# 4_cyber60-2_power.net
KiCad netlist of a schematic drawn in Altium Designer
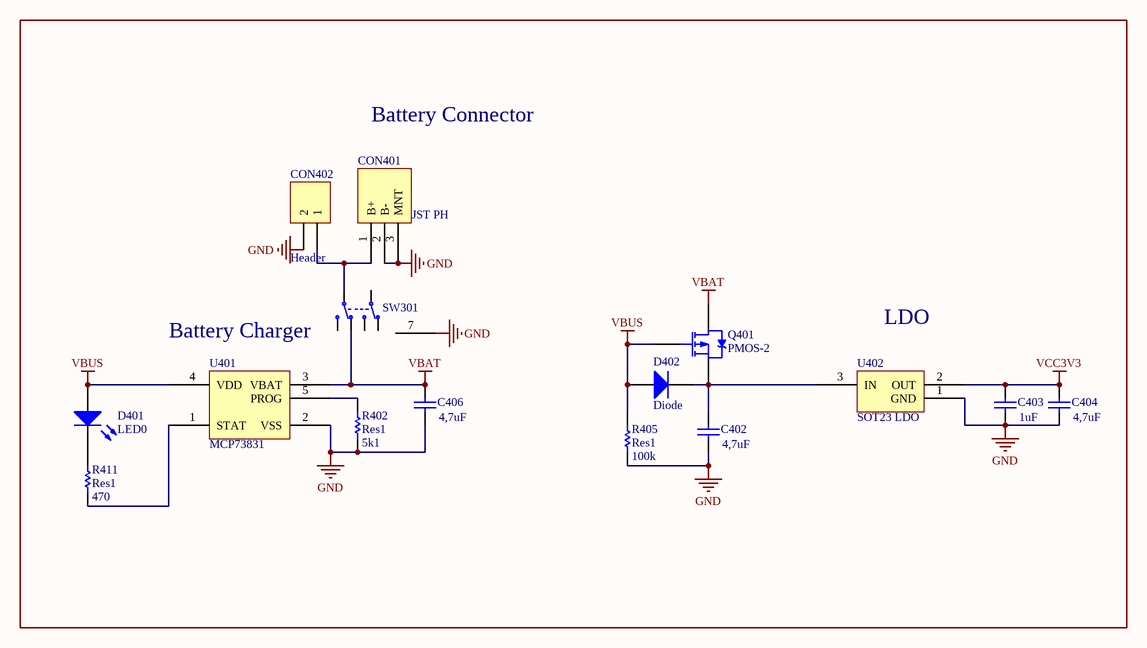
[diagram p0: 4_cyber60-2_power.SchDoc]

(export (version "E")
  (design (tool "Eeschema 10.0.6"))
  (components
    (comp (ref "C402")
      (value "4,7uF")
      (footprint "C0603[1608]")
      (description "Capacitor")
      (fields (field (name "LCSC PART #") "C19666") (field (name "MRF.PART") "CL10A475KO8NNNC"))
      (libsource (lib "Miscellaneous Devices") (part "Cap"))
    )
    (comp (ref "C403")
      (value "1uF")
      (footprint "C0603[1608]")
      (description "Capacitor")
      (fields (field (name "MFG") "KEMET") (field (name "LCSC PART #") "C15849"))
      (libsource (lib "Miscellaneous Devices") (part "Cap"))
    )
    (comp (ref "C404")
      (value "4,7uF")
      (footprint "C0603[1608]")
      (description "Capacitor")
      (fields (field (name "LCSC PART #") "C19666") (field (name "MRF.PART") "CL10A475KO8NNNC"))
      (libsource (lib "Miscellaneous Devices") (part "Cap"))
    )
    (comp (ref "C406")
      (value "4,7uF")
      (footprint "C0603[1608]")
      (description "Capacitor")
      (fields (field (name "LCSC PART #") "C19666") (field (name "MRF.PART") "CL10A475KO8NNNC"))
      (libsource (lib "Miscellaneous Devices") (part "Cap"))
    )
    (comp (ref "CON401")
      (value "JST PH")
      (footprint "JST SM02B-SRSS-TB")
      (fields (field (name "LCSC PART #") "C160402") (field (name "MRF.PART") "SM02B-SRSS-TB(LF)(SN)"))
      (libsource (lib "Keebs") (part "JST S2B-PH-SM4-TB"))
    )
    (comp (ref "CON402")
      (value "Header")
      (footprint "Keebs:JST S2B-PH-K(LF)(SN)")
      (description "Header, 2-Pin")
      (fields (field (name "LCSC PART #") "C265016") (field (name "MRF.PART") "S2B-PH-K(LF)(SN)"))
      (libsource (lib "Miscellaneous Connectors") (part "Header 2"))
    )
    (comp (ref "D401")
      (value "LED0")
      (footprint "LED0603[1608]")
      (description "Typical INFRARED GaAs LED")
      (fields (field (name "LCSC PART #") "C72038") (field (name "MRF.PART") "19-213/Y2C-CQ2R2L/3T(CY)"))
      (libsource (lib "Miscellaneous Devices") (part "LED0"))
    )
    (comp (ref "D402")
      (value "Diode")
      (footprint "SOD-123")
      (description "Default Diode")
      (fields (field (name "LCSC PART #") "C8598") (field (name "MRF.PART") "B5819W"))
      (libsource (lib "Miscellaneous Devices") (part "Diode"))
    )
    (comp (ref "Q401")
      (value "PMOS-2")
      (footprint "SOT-23-3")
      (description "P-Channel Power MOSFET")
      (fields (field (name "MRF.PART") "SI2301CDS-T1-GE3") (field (name "LCSC PART #") "C10487"))
      (libsource (lib "Miscellaneous Devices") (part "PMOS-2"))
    )
    (comp (ref "R402")
      (value "Res1")
      (footprint "R0603[1608]")
      (description "Resistor")
      (fields
        (field (name "ALTIUM_VALUE") "5k1")
        (field (name "MFG") "Panasonic Electronic Components")
        (field (name "LCSC PART #") "C23186")
      )
      (libsource (lib "Miscellaneous Devices") (part "Res1"))
    )
    (comp (ref "R405")
      (value "Res1")
      (footprint "R0603[1608]")
      (description "Resistor")
      (fields
        (field (name "ALTIUM_VALUE") "100k")
        (field (name "MRF.PART") "0603WAF1003T5E")
        (field (name "LCSC PART #") "C25803")
      )
      (libsource (lib "Miscellaneous Devices") (part "Res1"))
    )
    (comp (ref "R411")
      (value "Res1")
      (footprint "R0603[1608]")
      (description "Resistor")
      (fields
        (field (name "ALTIUM_VALUE") "470")
        (field (name "MFG") "Panasonic Electronic Components")
        (field (name "LCSC PART #") "C23179")
      )
      (libsource (lib "Miscellaneous Devices") (part "Res1"))
    )
    (comp (ref "SW301")
      (value "~")
      (footprint "AlpsAlpine SSSS820201")
      (description "Slide Switch DPDT")
      (fields (field (name "MRF.PART") "SSSS820201") (field (name "LCSC PART #") "C160879"))
      (libsource (lib "Keebs") (part "MKH-22D14-G2-B"))
    )
    (comp (ref "U401")
      (value "MCP73831")
      (footprint "SOT-23-5")
      (fields (field (name "LCSC PART #") "C32574") (field (name "MRF.PART") "TP4054"))
      (libsource (lib "Keebs") (part "MCP73831"))
    )
    (comp (ref "U402")
      (value "SOT23 LDO")
      (footprint "SOT-23-3")
      (fields
        (field (name "LCSC PART #") "C5446")
        (field (name "MRF.PART") "XC6206P332MR")
        (field (name "MFG") "Texas Instruments")
      )
      (libsource (lib "Keebs") (part "SOT23 LDO"))
    )
  )
  (nets
    (net (code "1") (name "GND") (class "Default")
      (node (ref "C402") (pin "1") (pinfunction "1_1") (pintype "passive"))
      (node (ref "C403") (pin "1") (pinfunction "1_1") (pintype "passive"))
      (node (ref "C404") (pin "1") (pinfunction "1_1") (pintype "passive"))
      (node (ref "C406") (pin "1") (pinfunction "1_1") (pintype "passive"))
      (node (ref "CON401") (pin "2") (pinfunction "B-_2") (pintype "passive"))
      (node (ref "CON401") (pin "3") (pinfunction "MNT_3") (pintype "passive"))
      (node (ref "CON402") (pin "2") (pinfunction "2_2") (pintype "passive"))
      (node (ref "R402") (pin "2") (pinfunction "2_2") (pintype "passive"))
      (node (ref "R405") (pin "2") (pinfunction "2_2") (pintype "passive"))
      (node (ref "SW301") (pin "7") (pinfunction "MNT_7") (pintype "passive"))
      (node (ref "U401") (pin "2") (pinfunction "VSS_2") (pintype "passive"))
      (node (ref "U402") (pin "1") (pinfunction "GND_1") (pintype "passive"))
    )
    (net (code "2") (name "Net-(CON401-B+)") (class "Default")
      (node (ref "CON401") (pin "1") (pinfunction "B+_1") (pintype "passive"))
      (node (ref "CON402") (pin "1") (pinfunction "1_1") (pintype "passive"))
      (node (ref "SW301") (pin "5") (pinfunction "COM-2_5") (pintype "passive"))
    )
    (net (code "3") (name "Net-(D401-K)") (class "Default")
      (node (ref "D401") (pin "2") (pinfunction "K_2") (pintype "passive"))
      (node (ref "R411") (pin "2") (pinfunction "2_2") (pintype "passive"))
    )
    (net (code "4") (name "Net-(D402-K)") (class "Default")
      (node (ref "C402") (pin "2") (pinfunction "2_2") (pintype "passive"))
      (node (ref "D402") (pin "2") (pinfunction "K_2") (pintype "passive"))
      (node (ref "Q401") (pin "2") (pinfunction "S_2") (pintype "passive"))
      (node (ref "U402") (pin "3") (pinfunction "IN_3") (pintype "passive"))
    )
    (net (code "5") (name "Net-(U401-PROG)") (class "Default")
      (node (ref "R402") (pin "1") (pinfunction "1_1") (pintype "passive"))
      (node (ref "U401") (pin "5") (pinfunction "PROG_5") (pintype "passive"))
    )
    (net (code "6") (name "Net-(U401-STAT)") (class "Default")
      (node (ref "R411") (pin "1") (pinfunction "1_1") (pintype "passive"))
      (node (ref "U401") (pin "1") (pinfunction "STAT_1") (pintype "passive"))
    )
    (net (code "7") (name "VBAT") (class "Default")
      (node (ref "C406") (pin "2") (pinfunction "2_2") (pintype "passive"))
      (node (ref "Q401") (pin "3") (pinfunction "D_3") (pintype "passive"))
      (node (ref "SW301") (pin "6") (pinfunction "N.C-2_6") (pintype "passive"))
      (node (ref "U401") (pin "3") (pinfunction "VBAT_3") (pintype "passive"))
    )
    (net (code "8") (name "VBUS") (class "Default")
      (node (ref "D401") (pin "1") (pinfunction "A_1") (pintype "passive"))
      (node (ref "D402") (pin "1") (pinfunction "A_1") (pintype "passive"))
      (node (ref "Q401") (pin "1") (pinfunction "G_1") (pintype "passive"))
      (node (ref "R405") (pin "1") (pinfunction "1_1") (pintype "passive"))
      (node (ref "U401") (pin "4") (pinfunction "VDD_4") (pintype "passive"))
    )
    (net (code "9") (name "VCC3V3") (class "Default")
      (node (ref "C403") (pin "2") (pinfunction "2_2") (pintype "passive"))
      (node (ref "C404") (pin "2") (pinfunction "2_2") (pintype "passive"))
      (node (ref "U402") (pin "2") (pinfunction "OUT_2") (pintype "passive"))
    )
    (net (code "10") (name "unconnected-(SW301-COM-1-Pad2)") (class "Default")
      (node (ref "SW301") (pin "2") (pinfunction "COM-1_2") (pintype "passive"))
    )
    (net (code "11") (name "unconnected-(SW301-N.C-1-Pad3)") (class "Default")
      (node (ref "SW301") (pin "3") (pinfunction "N.C-1_3") (pintype "passive"))
    )
    (net (code "12") (name "unconnected-(SW301-N.O-1-Pad1)") (class "Default")
      (node (ref "SW301") (pin "1") (pinfunction "N.O-1_1") (pintype "passive"))
    )
    (net (code "13") (name "unconnected-(SW301-N.O-2-Pad4)") (class "Default")
      (node (ref "SW301") (pin "4") (pinfunction "N.O-2_4") (pintype "passive"))
    )
  )
)
